# usb.net
KiCad netlist of a schematic drawn in Altium Designer
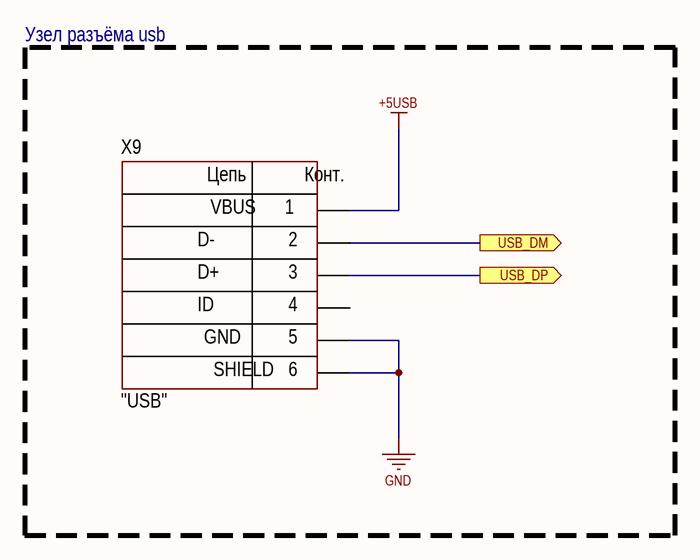
[diagram p0: Узел разъёма usb.SchDoc]

(export (version "E")
  (design (tool "Eeschema 10.0.6"))
  (components
    (comp (ref "X9")
      (value "~")
      (footprint "CON: USB micro-A (ZX62-B-5PA)")
      (fields
        (field (name "MANUFACTURER") "Hirose Electric")
        (field (name "VALUEMANUFACTURERPARTNUMBER") "USB micro B")
        (field (name "PARTNUMBER") "ZX62-B-5PA")
        (field (name "COMMENTTEXT") "\"USB\"")
      )
      (libsource (lib "connector") (part "Connector_USB_micro_B"))
    )
  )
  (nets
    (net (code "1") (name "+5USB") (class "Default") (node (ref "X9") (pin "1") (pintype "passive")))
    (net (code "2") (name "/USB_DM") (class "Default")
      (node (ref "X9") (pin "2") (pinfunction "2_2") (pintype "passive"))
    )
    (net (code "3") (name "/USB_DP") (class "Default")
      (node (ref "X9") (pin "3") (pinfunction "3_3") (pintype "passive"))
    )
    (net (code "4") (name "GND") (class "Default")
      (node (ref "X9") (pin "0") (pinfunction "0_0") (pintype "passive"))
      (node (ref "X9") (pin "5") (pinfunction "5_5") (pintype "passive"))
    )
    (net (code "5") (name "unconnected-(X9-Pad4)") (class "Default")
      (node (ref "X9") (pin "4") (pinfunction "4_4") (pintype "passive"))
    )
  )
)
